# Hikikomori-base-esp32c6-dev-v0_1.net
KiCad netlist of a schematic drawn in EasyEDA Pro
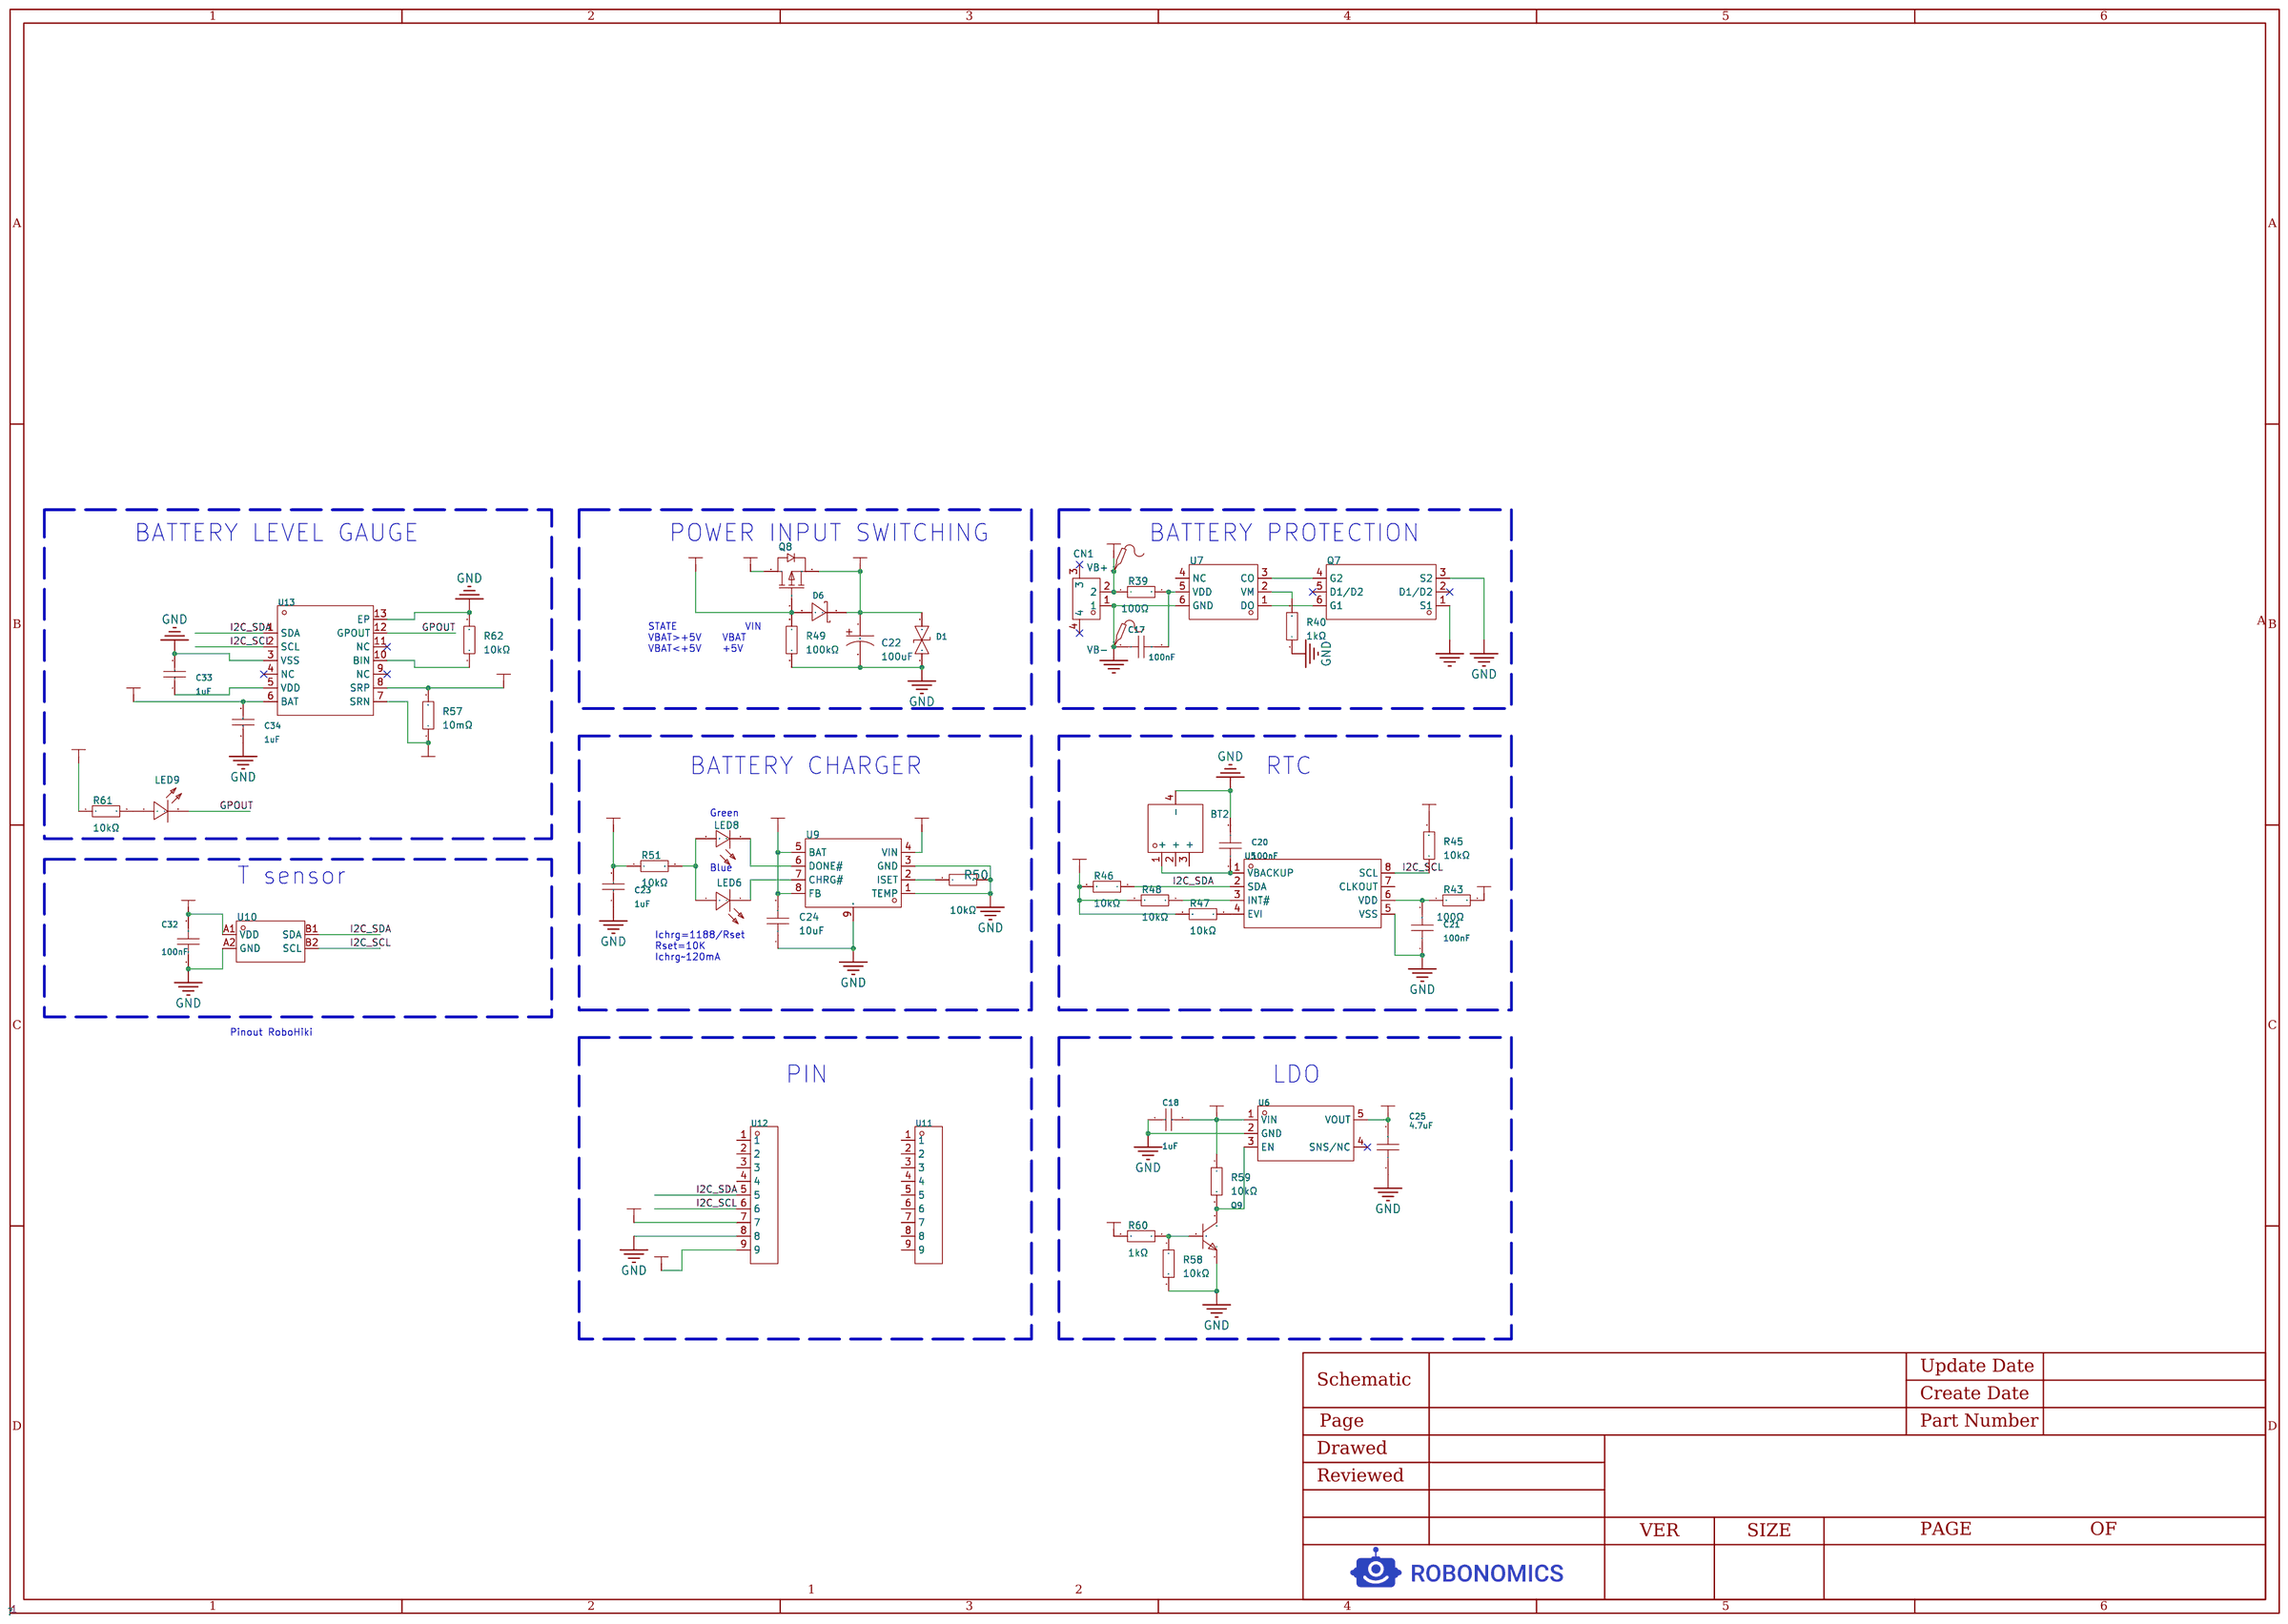
[diagram p0: schematic sheet]

(export (version "E")
  (design (tool "Eeschema 10.0.6"))
  (components
    (comp (ref "BT2")
      (value "MY-521-01")
      (footprint "easyedapro:BAT-SMD_MY-521-01")
      (fields (field (name "Manufacturer") "MYOUNG(美阳)"))
      (libsource (lib "easyedapro") (part "MY-521-01"))
    )
    (comp (ref "C17")
      (value "100nF")
      (footprint "easyedapro:C0402")
      (fields
        (field (name "Manufacturer Part") "CC0402KRX7R7BB104")
        (field (name "Manufacturer") "YAGEO(国巨)")
      )
      (libsource (lib "easyedapro") (part "CC0402KRX7R7BB104"))
    )
    (comp (ref "C18")
      (value "1uF")
      (footprint "easyedapro:C0402")
      (fields
        (field (name "Manufacturer Part") "CL05A105KO5NNNC")
        (field (name "Manufacturer") "SAMSUNG(三星)")
      )
      (libsource (lib "easyedapro") (part "CL05A105KO5NNNC"))
    )
    (comp (ref "C20")
      (value "100nF")
      (footprint "easyedapro:C0402")
      (fields
        (field (name "Manufacturer Part") "CC0402KRX7R7BB104")
        (field (name "Manufacturer") "YAGEO(国巨)")
      )
      (libsource (lib "easyedapro") (part "CC0402KRX7R7BB104"))
    )
    (comp (ref "C21")
      (value "100nF")
      (footprint "easyedapro:C0402")
      (fields
        (field (name "Manufacturer Part") "CC0402KRX7R7BB104")
        (field (name "Manufacturer") "YAGEO(国巨)")
      )
      (libsource (lib "easyedapro") (part "CC0402KRX7R7BB104"))
    )
    (comp (ref "C22")
      (value "100uF")
      (footprint "easyedapro:CAP-SMD_L3.5-W2.8-R-RD")
      (fields
        (field (name "Manufacturer Part") "293D107X96R3B2TE3")
        (field (name "Manufacturer") "VISHAY(威世)")
      )
      (libsource (lib "easyedapro") (part "293D107X96R3B2TE3"))
    )
    (comp (ref "C23")
      (value "1uF")
      (footprint "easyedapro:C0402")
      (fields
        (field (name "Manufacturer Part") "CL05A105KO5NNNC")
        (field (name "Manufacturer") "SAMSUNG(三星)")
      )
      (libsource (lib "easyedapro") (part "CL05A105KO5NNNC"))
    )
    (comp (ref "C24")
      (value "10uF")
      (footprint "easyedapro:C0402")
      (fields
        (field (name "Manufacturer Part") "CL05A106MP5NUNC")
        (field (name "Manufacturer") "SAMSUNG(三星)")
      )
      (libsource (lib "easyedapro") (part "CL05A106MP5NUNC_C315248"))
    )
    (comp (ref "C25")
      (value "4.7uF")
      (footprint "easyedapro:C0402")
      (fields
        (field (name "Manufacturer Part") "CL05A475KP5NRNC")
        (field (name "Manufacturer") "SAMSUNG(三星)")
      )
      (libsource (lib "easyedapro") (part "CL05A475KP5NRNC"))
    )
    (comp (ref "C32")
      (value "100nF")
      (footprint "easyedapro:C0402")
      (fields
        (field (name "Manufacturer Part") "CC0402KRX7R7BB104")
        (field (name "Manufacturer") "YAGEO(国巨)")
      )
      (libsource (lib "easyedapro") (part "CC0402KRX7R7BB104"))
    )
    (comp (ref "C33")
      (value "1uF")
      (footprint "easyedapro:C0402")
      (fields
        (field (name "Manufacturer Part") "CL05A105KO5NNNC")
        (field (name "Manufacturer") "SAMSUNG(三星)")
      )
      (libsource (lib "easyedapro") (part "CL05A105KO5NNNC"))
    )
    (comp (ref "C34")
      (value "1uF")
      (footprint "easyedapro:C0402")
      (fields
        (field (name "Manufacturer Part") "CL05A105KO5NNNC")
        (field (name "Manufacturer") "SAMSUNG(三星)")
      )
      (libsource (lib "easyedapro") (part "CL05A105KO5NNNC"))
    )
    (comp (ref "CN1")
      (value "A2001WR-S-2P")
      (footprint "easyedapro:CONN-SMD_2P-P2.00_A2001WR-S-2P")
      (fields (field (name "Manufacturer") "CNJM(九木精密)"))
      (libsource (lib "easyedapro") (part "A2001WR-S-2P_C375128"))
    )
    (comp (ref "D1")
      (value "LESD5D5.0CT1G")
      (footprint "easyedapro:SOD-523_L1.2-W0.8-LS1.6-BI")
      (fields (field (name "Manufacturer") "LRC(乐山无线电)"))
      (libsource (lib "easyedapro") (part "LESD5D5.0CT1G"))
    )
    (comp (ref "D6")
      (value "BAT60AE6327")
      (footprint "easyedapro:SOD-323_L1.8-W1.3-LS2.5-RD")
      (description "Forward Voltage (Vf@If):370mV@1A Reverse Voltage (Vr):10V Average Rectified Current (Io):3A")
      (fields (field (name "Manufacturer") "Infineon(英飞凌)"))
      (libsource (lib "easyedapro") (part "BAT60AE6327HTSA1"))
    )
    (comp (ref "LED6")
      (value "16-213/BHC-AN1P2/3T")
      (footprint "easyedapro:LED0402-R-RD")
      (description "Emitted Color:Blue")
      (fields (field (name "Manufacturer") "EVERLIGHT(亿光)"))
      (libsource (lib "easyedapro") (part "16-213/BHC-AN1P2/3T"))
    )
    (comp (ref "LED8")
      (value "16-213/GHC-YR1S1/3T")
      (footprint "easyedapro:LED0402-R-RD")
      (fields (field (name "Manufacturer") "EVERLIGHT(亿光)"))
      (libsource (lib "easyedapro") (part "16-213/GHC-YR1S1/3T"))
    )
    (comp (ref "LED9")
      (value "16-213UYOC/S530-A2/TR8")
      (footprint "easyedapro:LED0402-R-RD")
      (description "Emitted Color:Orange")
      (fields (field (name "Manufacturer") "EVERLIGHT(亿光)"))
      (libsource (lib "easyedapro") (part "16-213UYOC/S530-A2/TR8"))
    )
    (comp (ref "Q7")
      (value "SL8205S")
      (footprint "easyedapro:SOT-23-6_L2.9-W1.6-P0.95-LS2.8-BL")
      (fields (field (name "Manufacturer") "Slkor(萨科微)"))
      (libsource (lib "easyedapro") (part "SL8205S"))
    )
    (comp (ref "Q8")
      (value "CJ2301 S1")
      (footprint "easyedapro:SOT-23-3_L3.0-W1.7-P0.95-LS2.9-BR")
      (fields (field (name "Manufacturer") "CJ(江苏长电/长晶)"))
      (libsource (lib "easyedapro") (part "CJ2301 S1"))
    )
    (comp (ref "Q9")
      (value "2N3904S-RTK/PS")
      (footprint "easyedapro:SOT-23-3_L2.9-W1.3-P1.90-LS2.4-TR")
      (fields (field (name "Manufacturer") "KEC"))
      (libsource (lib "easyedapro") (part "2n3904S-RTK/PS_C18536"))
    )
    (comp (ref "R39")
      (value "100Ω")
      (footprint "easyedapro:R0402")
      (fields (field (name "Manufacturer Part") "RC0402FR-07100RL") (field (name "Manufacturer") "YAGEO(国巨)"))
      (libsource (lib "easyedapro") (part "RC0402FR-07100RL"))
    )
    (comp (ref "R40")
      (value "1kΩ")
      (footprint "easyedapro:R0402")
      (fields (field (name "Manufacturer Part") "RC0402FR-071KL") (field (name "Manufacturer") "YAGEO(国巨)"))
      (libsource (lib "easyedapro") (part "RC0402FR-071KL"))
    )
    (comp (ref "R43")
      (value "100Ω")
      (footprint "easyedapro:R0402")
      (fields (field (name "Manufacturer Part") "RC0402FR-07100RL") (field (name "Manufacturer") "YAGEO(国巨)"))
      (libsource (lib "easyedapro") (part "RC0402FR-07100RL"))
    )
    (comp (ref "R45")
      (value "10kΩ")
      (footprint "easyedapro:R0402")
      (fields (field (name "Manufacturer Part") "RC0402FR-0710KL") (field (name "Manufacturer") "YAGEO(国巨)"))
      (libsource (lib "easyedapro") (part "RC0402FR-0710KL"))
    )
    (comp (ref "R46")
      (value "10kΩ")
      (footprint "easyedapro:R0402")
      (fields (field (name "Manufacturer Part") "RC0402FR-0710KL") (field (name "Manufacturer") "YAGEO(国巨)"))
      (libsource (lib "easyedapro") (part "RC0402FR-0710KL"))
    )
    (comp (ref "R47")
      (value "10kΩ")
      (footprint "easyedapro:R0402")
      (fields (field (name "Manufacturer Part") "RC0402FR-0710KL") (field (name "Manufacturer") "YAGEO(国巨)"))
      (libsource (lib "easyedapro") (part "RC0402FR-0710KL"))
    )
    (comp (ref "R48")
      (value "10kΩ")
      (footprint "easyedapro:R0402")
      (fields (field (name "Manufacturer Part") "RC0402FR-0710KL") (field (name "Manufacturer") "YAGEO(国巨)"))
      (libsource (lib "easyedapro") (part "RC0402FR-0710KL"))
    )
    (comp (ref "R49")
      (value "100kΩ")
      (footprint "easyedapro:R0402")
      (fields (field (name "Manufacturer Part") "RC0402FR-07100KL") (field (name "Manufacturer") "YAGEO(国巨)"))
      (libsource (lib "easyedapro") (part "RC0402FR-07100KL"))
    )
    (comp (ref "R50")
      (value "10kΩ")
      (footprint "easyedapro:R0603")
      (fields
        (field (name "Manufacturer Part") "0603WAF1002T5E")
        (field (name "Manufacturer") "UNI-ROYAL(厚声)")
      )
      (libsource (lib "easyedapro") (part "0603WAF1002T5E"))
    )
    (comp (ref "R51")
      (value "10kΩ")
      (footprint "easyedapro:R0402")
      (fields (field (name "Manufacturer Part") "RC0402FR-0710KL") (field (name "Manufacturer") "YAGEO(国巨)"))
      (libsource (lib "easyedapro") (part "RC0402FR-0710KL"))
    )
    (comp (ref "R57")
      (value "10mΩ")
      (footprint "easyedapro:R0603")
      (fields
        (field (name "Manufacturer Part") "STE0603MW50R010F")
        (field (name "Manufacturer") "WALTER(华德)")
      )
      (libsource (lib "easyedapro") (part "STE0603MW50R010F"))
    )
    (comp (ref "R58")
      (value "10kΩ")
      (footprint "easyedapro:R0402")
      (fields (field (name "Manufacturer Part") "RC0402FR-0710KL") (field (name "Manufacturer") "YAGEO(国巨)"))
      (libsource (lib "easyedapro") (part "RC0402FR-0710KL"))
    )
    (comp (ref "R59")
      (value "10kΩ")
      (footprint "easyedapro:R0402")
      (fields (field (name "Manufacturer Part") "RC0402FR-0710KL") (field (name "Manufacturer") "YAGEO(国巨)"))
      (libsource (lib "easyedapro") (part "RC0402FR-0710KL"))
    )
    (comp (ref "R60")
      (value "1kΩ")
      (footprint "easyedapro:R0402")
      (fields (field (name "Manufacturer Part") "RC0402FR-071KL") (field (name "Manufacturer") "YAGEO(国巨)"))
      (libsource (lib "easyedapro") (part "RC0402FR-071KL"))
    )
    (comp (ref "R61")
      (value "10kΩ")
      (footprint "easyedapro:R0402")
      (fields (field (name "Manufacturer Part") "RC0402FR-0710KL") (field (name "Manufacturer") "YAGEO(国巨)"))
      (libsource (lib "easyedapro") (part "RC0402FR-0710KL"))
    )
    (comp (ref "R62")
      (value "10kΩ")
      (footprint "easyedapro:R0402")
      (fields (field (name "Manufacturer Part") "RC0402FR-0710KL") (field (name "Manufacturer") "YAGEO(国巨)"))
      (libsource (lib "easyedapro") (part "RC0402FR-0710KL"))
    )
    (comp (ref "U5")
      (value "RV-3032-C7-32.768KHZ-2.5PPM-TA-QA")
      (footprint "easyedapro:DFN-8_L3.2-W1.5-P0.9-BL")
      (fields (field (name "Manufacturer") "Micro Crystal(瑞士微晶)"))
      (libsource (lib "easyedapro") (part "RV-3032-C7-32.768KHZ-2.5PPM-TA-QA"))
    )
    (comp (ref "U6")
      (value "RT9078-33GJ5")
      (footprint "easyedapro:TSOT-23-5_L2.9-W1.6-P0.95-LS2.8-BR")
      (fields (field (name "Manufacturer") "RICHTEK(立锜)"))
      (libsource (lib "easyedapro") (part "RT9078-33GJ5"))
    )
    (comp (ref "U7")
      (value "DW01A")
      (footprint "easyedapro:SOT-23-6_L2.9-W1.6-P0.95-LS2.8-BL")
      (fields (field (name "Manufacturer") "TF(拓锋)"))
      (libsource (lib "easyedapro") (part "DW01A_C436931"))
    )
    (comp (ref "U9")
      (value "CN3165")
      (footprint "easyedapro:DFN-8_L3.0-W3.0-P0.50-BL-EP")
      (fields (field (name "Manufacturer") "CONSONANCE(上海如韵)"))
      (libsource (lib "easyedapro") (part "CN3165"))
    )
    (comp (ref "U10")
      (value "MAX31875R0TZS+T")
      (footprint "easyedapro:WLP-4_L0.8-W0.8-R2-C2-P0.40-TL")
      (description "Supply Voltage:1.6V~3.6V Supply Voltage:1.6V~3.6V")
      (fields (field (name "Manufacturer") "ADI(亚德诺)/MAXIM(美信)"))
      (libsource (lib "easyedapro") (part "MAX31875R0TZS+T"))
    )
    (comp (ref "U11")
      (value "XDZ254-1-09-Z-2.5-G1")
      (footprint "easyedapro:HDR-TH_9P-P2.54-V-M")
      (fields (field (name "Manufacturer") "XUNDA(讯答)"))
      (libsource (lib "easyedapro") (part "XDZ254-1-09-Z-2.5-G1"))
    )
    (comp (ref "U12")
      (value "XDZ254-1-09-Z-2.5-G1")
      (footprint "easyedapro:HDR-TH_9P-P2.54-V-M")
      (fields (field (name "Manufacturer") "XUNDA(讯答)"))
      (libsource (lib "easyedapro") (part "XDZ254-1-09-Z-2.5-G1"))
    )
    (comp (ref "U13")
      (value "BQ27441DRZR-G1B")
      (footprint "easyedapro:SON-12_L4.0-W2.5-P0.40-BL-EP")
      (fields (field (name "Manufacturer") "TI(德州仪器)"))
      (libsource (lib "easyedapro") (part "BQ27441DRZR-G1B"))
    )
    (comp (ref "VB+")
      (value "~")
      (footprint "easyedapro:Test-Point-0.5mm")
      (description "Test Point 测试点")
      (libsource (lib "easyedapro") (part "Test-Point"))
    )
    (comp (ref "VB-")
      (value "~")
      (footprint "easyedapro:Test-Point-0.5mm")
      (description "Test Point 测试点")
      (libsource (lib "easyedapro") (part "Test-Point"))
    )
  )
  (nets
    (net (code "1") (name "+5V") (class "Default")
      (node (ref "C23") (pin "2") (pinfunction "2_2") (pintype "input"))
      (node (ref "D6") (pin "2") (pinfunction "A_2") (pintype "input"))
      (node (ref "Q8") (pin "1") (pinfunction "G_1") (pintype "unspecified"))
      (node (ref "R49") (pin "2") (pinfunction "2_2") (pintype "input"))
      (node (ref "R51") (pin "1") (pinfunction "1_1") (pintype "input"))
      (node (ref "R60") (pin "2") (pinfunction "2_2") (pintype "input"))
      (node (ref "U12") (pin "9") (pinfunction "9_9") (pintype "input"))
      (node (ref "U9") (pin "4") (pinfunction "VIN_4") (pintype "input"))
    )
    (net (code "2") (name "/GPOUT") (class "Default")
      (node (ref "LED9") (pin "2") (pinfunction "K_2") (pintype "input"))
      (node (ref "U13") (pin "12") (pinfunction "GPOUT_12") (pintype "input"))
    )
    (net (code "3") (name "/I2C_SCL") (class "Default")
      (node (ref "R45") (pin "1") (pinfunction "1_1") (pintype "input"))
      (node (ref "U10") (pin "B2") (pinfunction "SCL_B2") (pintype "unspecified"))
      (node (ref "U12") (pin "6") (pinfunction "6_6") (pintype "input"))
      (node (ref "U13") (pin "2") (pinfunction "SCL_2") (pintype "input"))
      (node (ref "U5") (pin "8") (pinfunction "SCL_8") (pintype "input"))
    )
    (net (code "4") (name "/I2C_SDA") (class "Default")
      (node (ref "R46") (pin "1") (pinfunction "1_1") (pintype "input"))
      (node (ref "U10") (pin "B1") (pinfunction "SDA_B1") (pintype "unspecified"))
      (node (ref "U12") (pin "5") (pinfunction "5_5") (pintype "input"))
      (node (ref "U13") (pin "1") (pinfunction "SDA_1") (pintype "input"))
      (node (ref "U5") (pin "2") (pinfunction "SDA_2") (pintype "input"))
    )
    (net (code "5") (name "3V3") (class "Default")
      (node (ref "C25") (pin "2") (pinfunction "2_2") (pintype "input"))
      (node (ref "C32") (pin "2") (pinfunction "2_2") (pintype "input"))
      (node (ref "R43") (pin "2") (pinfunction "2_2") (pintype "input"))
      (node (ref "R45") (pin "2") (pinfunction "2_2") (pintype "input"))
      (node (ref "R46") (pin "2") (pinfunction "2_2") (pintype "input"))
      (node (ref "R47") (pin "2") (pinfunction "2_2") (pintype "input"))
      (node (ref "R48") (pin "2") (pinfunction "2_2") (pintype "input"))
      (node (ref "U10") (pin "A1") (pinfunction "VDD_A1") (pintype "unspecified"))
      (node (ref "U12") (pin "7") (pinfunction "7_7") (pintype "input"))
      (node (ref "U6") (pin "5") (pinfunction "VOUT_5") (pintype "input"))
    )
    (net (code "6") (name "GND") (class "Default")
      (node (ref "BT2") (pin "4") (pinfunction "-_4") (pintype "unspecified"))
      (node (ref "C18") (pin "1") (pinfunction "1_1") (pintype "input"))
      (node (ref "C20") (pin "2") (pinfunction "2_2") (pintype "input"))
      (node (ref "C21") (pin "1") (pinfunction "1_1") (pintype "input"))
      (node (ref "C22") (pin "2") (pinfunction "2_2") (pintype "unspecified"))
      (node (ref "C23") (pin "1") (pinfunction "1_1") (pintype "input"))
      (node (ref "C24") (pin "1") (pinfunction "1_1") (pintype "unspecified"))
      (node (ref "C25") (pin "1") (pinfunction "1_1") (pintype "input"))
      (node (ref "C32") (pin "1") (pinfunction "1_1") (pintype "input"))
      (node (ref "C33") (pin "2") (pinfunction "2_2") (pintype "input"))
      (node (ref "C34") (pin "1") (pinfunction "1_1") (pintype "input"))
      (node (ref "D1") (pin "2") (pinfunction "2_2") (pintype "input"))
      (node (ref "Q7") (pin "3") (pinfunction "S2_3") (pintype "unspecified"))
      (node (ref "Q9") (pin "1") (pinfunction "E_1") (pintype "input"))
      (node (ref "R40") (pin "1") (pinfunction "1_1") (pintype "input"))
      (node (ref "R49") (pin "1") (pinfunction "1_1") (pintype "input"))
      (node (ref "R50") (pin "2") (pinfunction "2_2") (pintype "input"))
      (node (ref "R58") (pin "2") (pinfunction "2_2") (pintype "input"))
      (node (ref "R62") (pin "2") (pinfunction "2_2") (pintype "input"))
      (node (ref "U10") (pin "A2") (pinfunction "GND_A2") (pintype "unspecified"))
      (node (ref "U12") (pin "8") (pinfunction "8_8") (pintype "input"))
      (node (ref "U13") (pin "13") (pinfunction "EP_13") (pintype "input"))
      (node (ref "U13") (pin "3") (pinfunction "VSS_3") (pintype "input"))
      (node (ref "U5") (pin "5") (pinfunction "VSS_5") (pintype "input"))
      (node (ref "U6") (pin "2") (pinfunction "GND_2") (pintype "input"))
      (node (ref "U9") (pin "1") (pinfunction "TEMP_1") (pintype "input"))
      (node (ref "U9") (pin "3") (pinfunction "GND_3") (pintype "input"))
      (node (ref "U9") (pin "9") (pinfunction "PAD_9") (pintype "input"))
    )
    (net (code "7") (name "Net-(LED6-A)") (class "Default")
      (node (ref "LED6") (pin "1") (pinfunction "A_1") (pintype "unspecified"))
      (node (ref "LED8") (pin "1") (pinfunction "A_1") (pintype "input"))
      (node (ref "R51") (pin "2") (pinfunction "2_2") (pintype "input"))
    )
    (net (code "8") (name "Net-(LED6-K)") (class "Default")
      (node (ref "LED6") (pin "2") (pinfunction "K_2") (pintype "unspecified"))
      (node (ref "U9") (pin "7") (pinfunction "CHRG#_7") (pintype "input"))
    )
    (net (code "9") (name "Net-(LED8-C)") (class "Default")
      (node (ref "LED8") (pin "2") (pinfunction "C_2") (pintype "input"))
      (node (ref "U9") (pin "6") (pinfunction "DONE#_6") (pintype "input"))
    )
    (net (code "10") (name "Net-(LED9-A)") (class "Default")
      (node (ref "LED9") (pin "1") (pinfunction "A_1") (pintype "input"))
      (node (ref "R61") (pin "2") (pinfunction "2_2") (pintype "input"))
    )
    (net (code "11") (name "Net-(Q7-G1)") (class "Default")
      (node (ref "Q7") (pin "6") (pinfunction "G1_6") (pintype "unspecified"))
      (node (ref "U7") (pin "1") (pinfunction "DO_1") (pintype "unspecified"))
    )
    (net (code "12") (name "Net-(Q7-G2)") (class "Default")
      (node (ref "Q7") (pin "4") (pinfunction "G2_4") (pintype "unspecified"))
      (node (ref "U7") (pin "3") (pinfunction "CO_3") (pintype "unspecified"))
    )
    (net (code "13") (name "Net-(Q9-B)") (class "Default")
      (node (ref "Q9") (pin "2") (pinfunction "B_2") (pintype "input"))
      (node (ref "R58") (pin "1") (pinfunction "1_1") (pintype "input"))
      (node (ref "R60") (pin "1") (pinfunction "1_1") (pintype "input"))
    )
    (net (code "14") (name "Net-(Q9-C)") (class "Default")
      (node (ref "Q9") (pin "3") (pinfunction "C_3") (pintype "input"))
      (node (ref "R59") (pin "2") (pinfunction "2_2") (pintype "input"))
      (node (ref "U6") (pin "3") (pinfunction "EN_3") (pintype "input"))
    )
    (net (code "15") (name "Net-(U5-EVI)") (class "Default")
      (node (ref "R47") (pin "1") (pinfunction "1_1") (pintype "input"))
      (node (ref "U5") (pin "4") (pinfunction "EVI_4") (pintype "input"))
    )
    (net (code "16") (name "Net-(U5-INT#)") (class "Default")
      (node (ref "R48") (pin "1") (pinfunction "1_1") (pintype "input"))
      (node (ref "U5") (pin "3") (pinfunction "INT#_3") (pintype "input"))
    )
    (net (code "17") (name "Net-(U5-VBACKUP)") (class "Default")
      (node (ref "BT2") (pin "1") (pinfunction "+_1") (pintype "unspecified"))
      (node (ref "C20") (pin "1") (pinfunction "1_1") (pintype "input"))
      (node (ref "U5") (pin "1") (pinfunction "VBACKUP_1") (pintype "input"))
    )
    (net (code "18") (name "Net-(U5-VDD)") (class "Default")
      (node (ref "C21") (pin "2") (pinfunction "2_2") (pintype "input"))
      (node (ref "R43") (pin "1") (pinfunction "1_1") (pintype "input"))
      (node (ref "U5") (pin "6") (pinfunction "VDD_6") (pintype "input"))
    )
    (net (code "19") (name "Net-(U7-VDD)") (class "Default")
      (node (ref "C17") (pin "2") (pinfunction "2_2") (pintype "input"))
      (node (ref "R39") (pin "2") (pinfunction "2_2") (pintype "input"))
      (node (ref "U7") (pin "5") (pinfunction "VDD_5") (pintype "unspecified"))
    )
    (net (code "20") (name "Net-(U7-VM)") (class "Default")
      (node (ref "R40") (pin "2") (pinfunction "2_2") (pintype "input"))
      (node (ref "U7") (pin "2") (pinfunction "VM_2") (pintype "unspecified"))
    )
    (net (code "21") (name "Net-(U9-ISET)") (class "Default")
      (node (ref "R50") (pin "1") (pinfunction "1_1") (pintype "input"))
      (node (ref "U9") (pin "2") (pinfunction "ISET_2") (pintype "input"))
    )
    (net (code "22") (name "Net-(U13-BIN)") (class "Default")
      (node (ref "R62") (pin "1") (pinfunction "1_1") (pintype "input"))
      (node (ref "U13") (pin "10") (pinfunction "BIN_10") (pintype "input"))
    )
    (net (code "23") (name "Net-(U13-VDD)") (class "Default")
      (node (ref "C33") (pin "1") (pinfunction "1_1") (pintype "input"))
      (node (ref "U13") (pin "5") (pinfunction "VDD_5") (pintype "input"))
    )
    (net (code "24") (name "VBAT+") (class "Default")
      (node (ref "Q8") (pin "3") (pinfunction "D_3") (pintype "unspecified"))
      (node (ref "R57") (pin "1") (pinfunction "1_1") (pintype "input"))
      (node (ref "R61") (pin "1") (pinfunction "1_1") (pintype "input"))
      (node (ref "U13") (pin "7") (pinfunction "SRN_7") (pintype "input"))
    )
    (net (code "25") (name "VBAT-") (class "Default")
      (node (ref "C17") (pin "1") (pinfunction "1_1") (pintype "input"))
      (node (ref "CN1") (pin "1") (pinfunction "1_1") (pintype "input"))
      (node (ref "Q7") (pin "1") (pinfunction "S1_1") (pintype "unspecified"))
      (node (ref "U7") (pin "6") (pinfunction "GND_6") (pintype "unspecified"))
      (node (ref "VB-") (pin "1") (pinfunction "1_1") (pintype "unspecified"))
    )
    (net (code "26") (name "VBAT0+") (class "Default")
      (node (ref "C24") (pin "2") (pinfunction "2_2") (pintype "unspecified"))
      (node (ref "C34") (pin "2") (pinfunction "2_2") (pintype "input"))
      (node (ref "CN1") (pin "2") (pinfunction "2_2") (pintype "input"))
      (node (ref "R39") (pin "1") (pinfunction "1_1") (pintype "input"))
      (node (ref "R57") (pin "2") (pinfunction "2_2") (pintype "input"))
      (node (ref "U13") (pin "6") (pinfunction "BAT_6") (pintype "input"))
      (node (ref "U13") (pin "8") (pinfunction "SRP_8") (pintype "input"))
      (node (ref "U9") (pin "5") (pinfunction "BAT_5") (pintype "input"))
      (node (ref "U9") (pin "8") (pinfunction "FB_8") (pintype "input"))
      (node (ref "VB+") (pin "1") (pinfunction "1_1") (pintype "unspecified"))
    )
    (net (code "27") (name "VIN") (class "Default")
      (node (ref "C18") (pin "2") (pinfunction "2_2") (pintype "input"))
      (node (ref "C22") (pin "1") (pinfunction "1_1") (pintype "unspecified"))
      (node (ref "D1") (pin "1") (pinfunction "1_1") (pintype "input"))
      (node (ref "D6") (pin "1") (pinfunction "K_1") (pintype "input"))
      (node (ref "Q8") (pin "2") (pinfunction "S_2") (pintype "unspecified"))
      (node (ref "R59") (pin "1") (pinfunction "1_1") (pintype "input"))
      (node (ref "U6") (pin "1") (pinfunction "VIN_1") (pintype "input"))
    )
    (net (code "28") (name "unconnected-(BT2-+-Pad2)") (class "Default")
      (node (ref "BT2") (pin "2") (pinfunction "+_2") (pintype "unspecified"))
    )
    (net (code "29") (name "unconnected-(BT2-+-Pad3)") (class "Default")
      (node (ref "BT2") (pin "3") (pinfunction "+_3") (pintype "unspecified"))
    )
    (net (code "30") (name "unconnected-(CN1-Pad3)") (class "Default")
      (node (ref "CN1") (pin "3") (pinfunction "3_3") (pintype "input+no_connect"))
    )
    (net (code "31") (name "unconnected-(CN1-Pad4)") (class "Default")
      (node (ref "CN1") (pin "4") (pinfunction "4_4") (pintype "input+no_connect"))
    )
    (net (code "32") (name "unconnected-(Q7-D1{slash}D2-Pad2)") (class "Default")
      (node (ref "Q7") (pin "2") (pinfunction "D1/D2_2") (pintype "unspecified+no_connect"))
    )
    (net (code "33") (name "unconnected-(Q7-D1{slash}D2-Pad5)") (class "Default")
      (node (ref "Q7") (pin "5") (pinfunction "D1/D2_5") (pintype "unspecified+no_connect"))
    )
    (net (code "34") (name "unconnected-(U5-CLKOUT-Pad7)") (class "Default")
      (node (ref "U5") (pin "7") (pinfunction "CLKOUT_7") (pintype "input"))
    )
    (net (code "35") (name "unconnected-(U6-SNS{slash}NC-Pad4)") (class "Default")
      (node (ref "U6") (pin "4") (pinfunction "SNS/NC_4") (pintype "input+no_connect"))
    )
    (net (code "36") (name "unconnected-(U7-NC-Pad4)") (class "Default")
      (node (ref "U7") (pin "4") (pinfunction "NC_4") (pintype "unspecified"))
    )
    (net (code "37") (name "unconnected-(U11-Pad1)") (class "Default")
      (node (ref "U11") (pin "1") (pinfunction "1_1") (pintype "input"))
    )
    (net (code "38") (name "unconnected-(U11-Pad2)") (class "Default")
      (node (ref "U11") (pin "2") (pinfunction "2_2") (pintype "input"))
    )
    (net (code "39") (name "unconnected-(U11-Pad3)") (class "Default")
      (node (ref "U11") (pin "3") (pinfunction "3_3") (pintype "input"))
    )
    (net (code "40") (name "unconnected-(U11-Pad4)") (class "Default")
      (node (ref "U11") (pin "4") (pinfunction "4_4") (pintype "input"))
    )
    (net (code "41") (name "unconnected-(U11-Pad5)") (class "Default")
      (node (ref "U11") (pin "5") (pinfunction "5_5") (pintype "input"))
    )
    (net (code "42") (name "unconnected-(U11-Pad6)") (class "Default")
      (node (ref "U11") (pin "6") (pinfunction "6_6") (pintype "input"))
    )
    (net (code "43") (name "unconnected-(U11-Pad7)") (class "Default")
      (node (ref "U11") (pin "7") (pinfunction "7_7") (pintype "input"))
    )
    (net (code "44") (name "unconnected-(U11-Pad8)") (class "Default")
      (node (ref "U11") (pin "8") (pinfunction "8_8") (pintype "input"))
    )
    (net (code "45") (name "unconnected-(U11-Pad9)") (class "Default")
      (node (ref "U11") (pin "9") (pinfunction "9_9") (pintype "input"))
    )
    (net (code "46") (name "unconnected-(U12-Pad1)") (class "Default")
      (node (ref "U12") (pin "1") (pinfunction "1_1") (pintype "input"))
    )
    (net (code "47") (name "unconnected-(U12-Pad2)") (class "Default")
      (node (ref "U12") (pin "2") (pinfunction "2_2") (pintype "input"))
    )
    (net (code "48") (name "unconnected-(U12-Pad3)") (class "Default")
      (node (ref "U12") (pin "3") (pinfunction "3_3") (pintype "input"))
    )
    (net (code "49") (name "unconnected-(U12-Pad4)") (class "Default")
      (node (ref "U12") (pin "4") (pinfunction "4_4") (pintype "input"))
    )
    (net (code "50") (name "unconnected-(U13-NC-Pad4)") (class "Default")
      (node (ref "U13") (pin "4") (pinfunction "NC_4") (pintype "input+no_connect"))
    )
    (net (code "51") (name "unconnected-(U13-NC-Pad9)") (class "Default")
      (node (ref "U13") (pin "9") (pinfunction "NC_9") (pintype "input+no_connect"))
    )
    (net (code "52") (name "unconnected-(U13-NC-Pad11)") (class "Default")
      (node (ref "U13") (pin "11") (pinfunction "NC_11") (pintype "input+no_connect"))
    )
  )
)
